# LED.net
KiCad netlist of a schematic drawn in Altium Designer
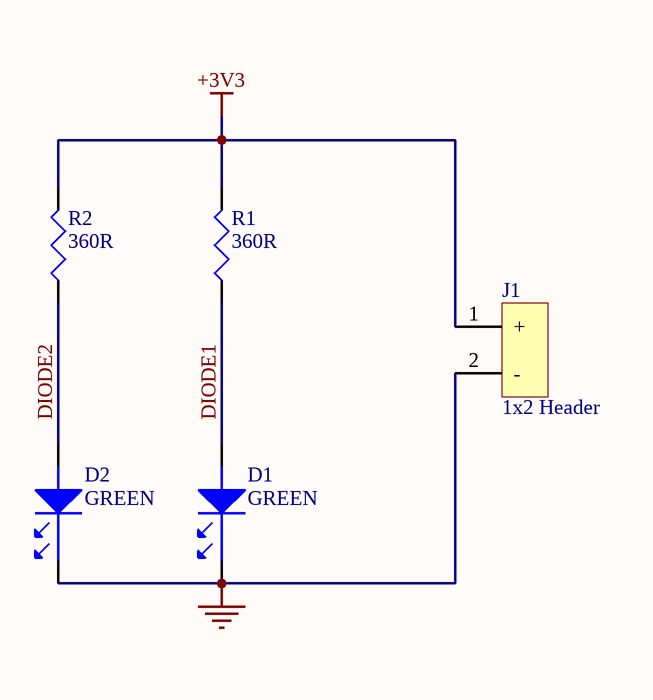
[diagram p0: LED.SchDoc]

(export (version "E")
  (design (tool "Eeschema 10.0.6"))
  (components
    (comp (ref "D1")
      (value "GREEN")
      (footprint "LED_LNJ626 GREEN")
      (description "PANASONIC - LNJ626W8CRA - LED, REINGRÜN, HIGH-BRIGHTNESS, 0603")
      (fields
        (field (name "MANUFACTURER") "Panasonic SSG")
        (field (name "MANUFACTURER PART NUMBER") "LNJ626W8CRA")
      )
      (libsource (lib "LED_Schlib") (part "LNJ626W8CRA"))
    )
    (comp (ref "D2")
      (value "GREEN")
      (footprint "LED_LNJ626 GREEN")
      (description "PANASONIC - LNJ626W8CRA - LED, REINGRÜN, HIGH-BRIGHTNESS, 0603")
      (fields
        (field (name "MANUFACTURER") "Panasonic SSG")
        (field (name "MANUFACTURER PART NUMBER") "LNJ626W8CRA")
      )
      (libsource (lib "LED_Schlib") (part "LNJ626W8CRA"))
    )
    (comp (ref "J1")
      (value "1x2 Header")
      (footprint "HDR1X2")
      (description "Conn Wire to Board HDR 2 POS 2.54mm Solder ST Thru-Hole Bag")
      (fields (field (name "MANUFACTURER") "Molex") (field (name "MANUFACTURER PART NUMBER") "22-29-2021"))
      (libsource (lib "LED_Schlib") (part "22-29-2021"))
    )
    (comp (ref "R1")
      (value "360R")
      (footprint "R_CRCW0805")
      (description "RES SMD 3.6 OHM 1% 1/8W 0805")
      (fields
        (field (name "MANUFACTURER") "Vishay Dale")
        (field (name "MANUFACTURER PART NUMBER") "CRCW08053R60FNEA")
      )
      (libsource (lib "LED_Schlib") (part "CRCW08053R60FNEA"))
    )
    (comp (ref "R2")
      (value "360R")
      (footprint "R_CRCW0805")
      (description "RES SMD 3.6 OHM 1% 1/8W 0805")
      (fields
        (field (name "MANUFACTURER") "Vishay Dale")
        (field (name "MANUFACTURER PART NUMBER") "CRCW08053R60FNEA")
      )
      (libsource (lib "LED_Schlib") (part "CRCW08053R60FNEA"))
    )
  )
  (nets
    (net (code "1") (name "+3V3") (class "Default")
      (node (ref "J1") (pin "1") (pinfunction "+_1") (pintype "passive"))
      (node (ref "R1") (pin "2") (pinfunction "2_2") (pintype "passive"))
      (node (ref "R2") (pin "2") (pinfunction "2_2") (pintype "passive"))
    )
    (net (code "2") (name "/DIODE1") (class "Default")
      (node (ref "D1") (pin "2") (pinfunction "2_2") (pintype "passive"))
      (node (ref "R1") (pin "1") (pinfunction "1_1") (pintype "passive"))
    )
    (net (code "3") (name "/DIODE2") (class "Default")
      (node (ref "D2") (pin "2") (pinfunction "2_2") (pintype "passive"))
      (node (ref "R2") (pin "1") (pinfunction "1_1") (pintype "passive"))
    )
    (net (code "4") (name "GND") (class "Default")
      (node (ref "D1") (pin "1") (pinfunction "1_1") (pintype "passive"))
      (node (ref "D2") (pin "1") (pinfunction "1_1") (pintype "passive"))
      (node (ref "J1") (pin "2") (pinfunction "-_2") (pintype "passive"))
    )
  )
)
